# ranback_bottom.net
KiCad netlist of a schematic drawn in EAGLE
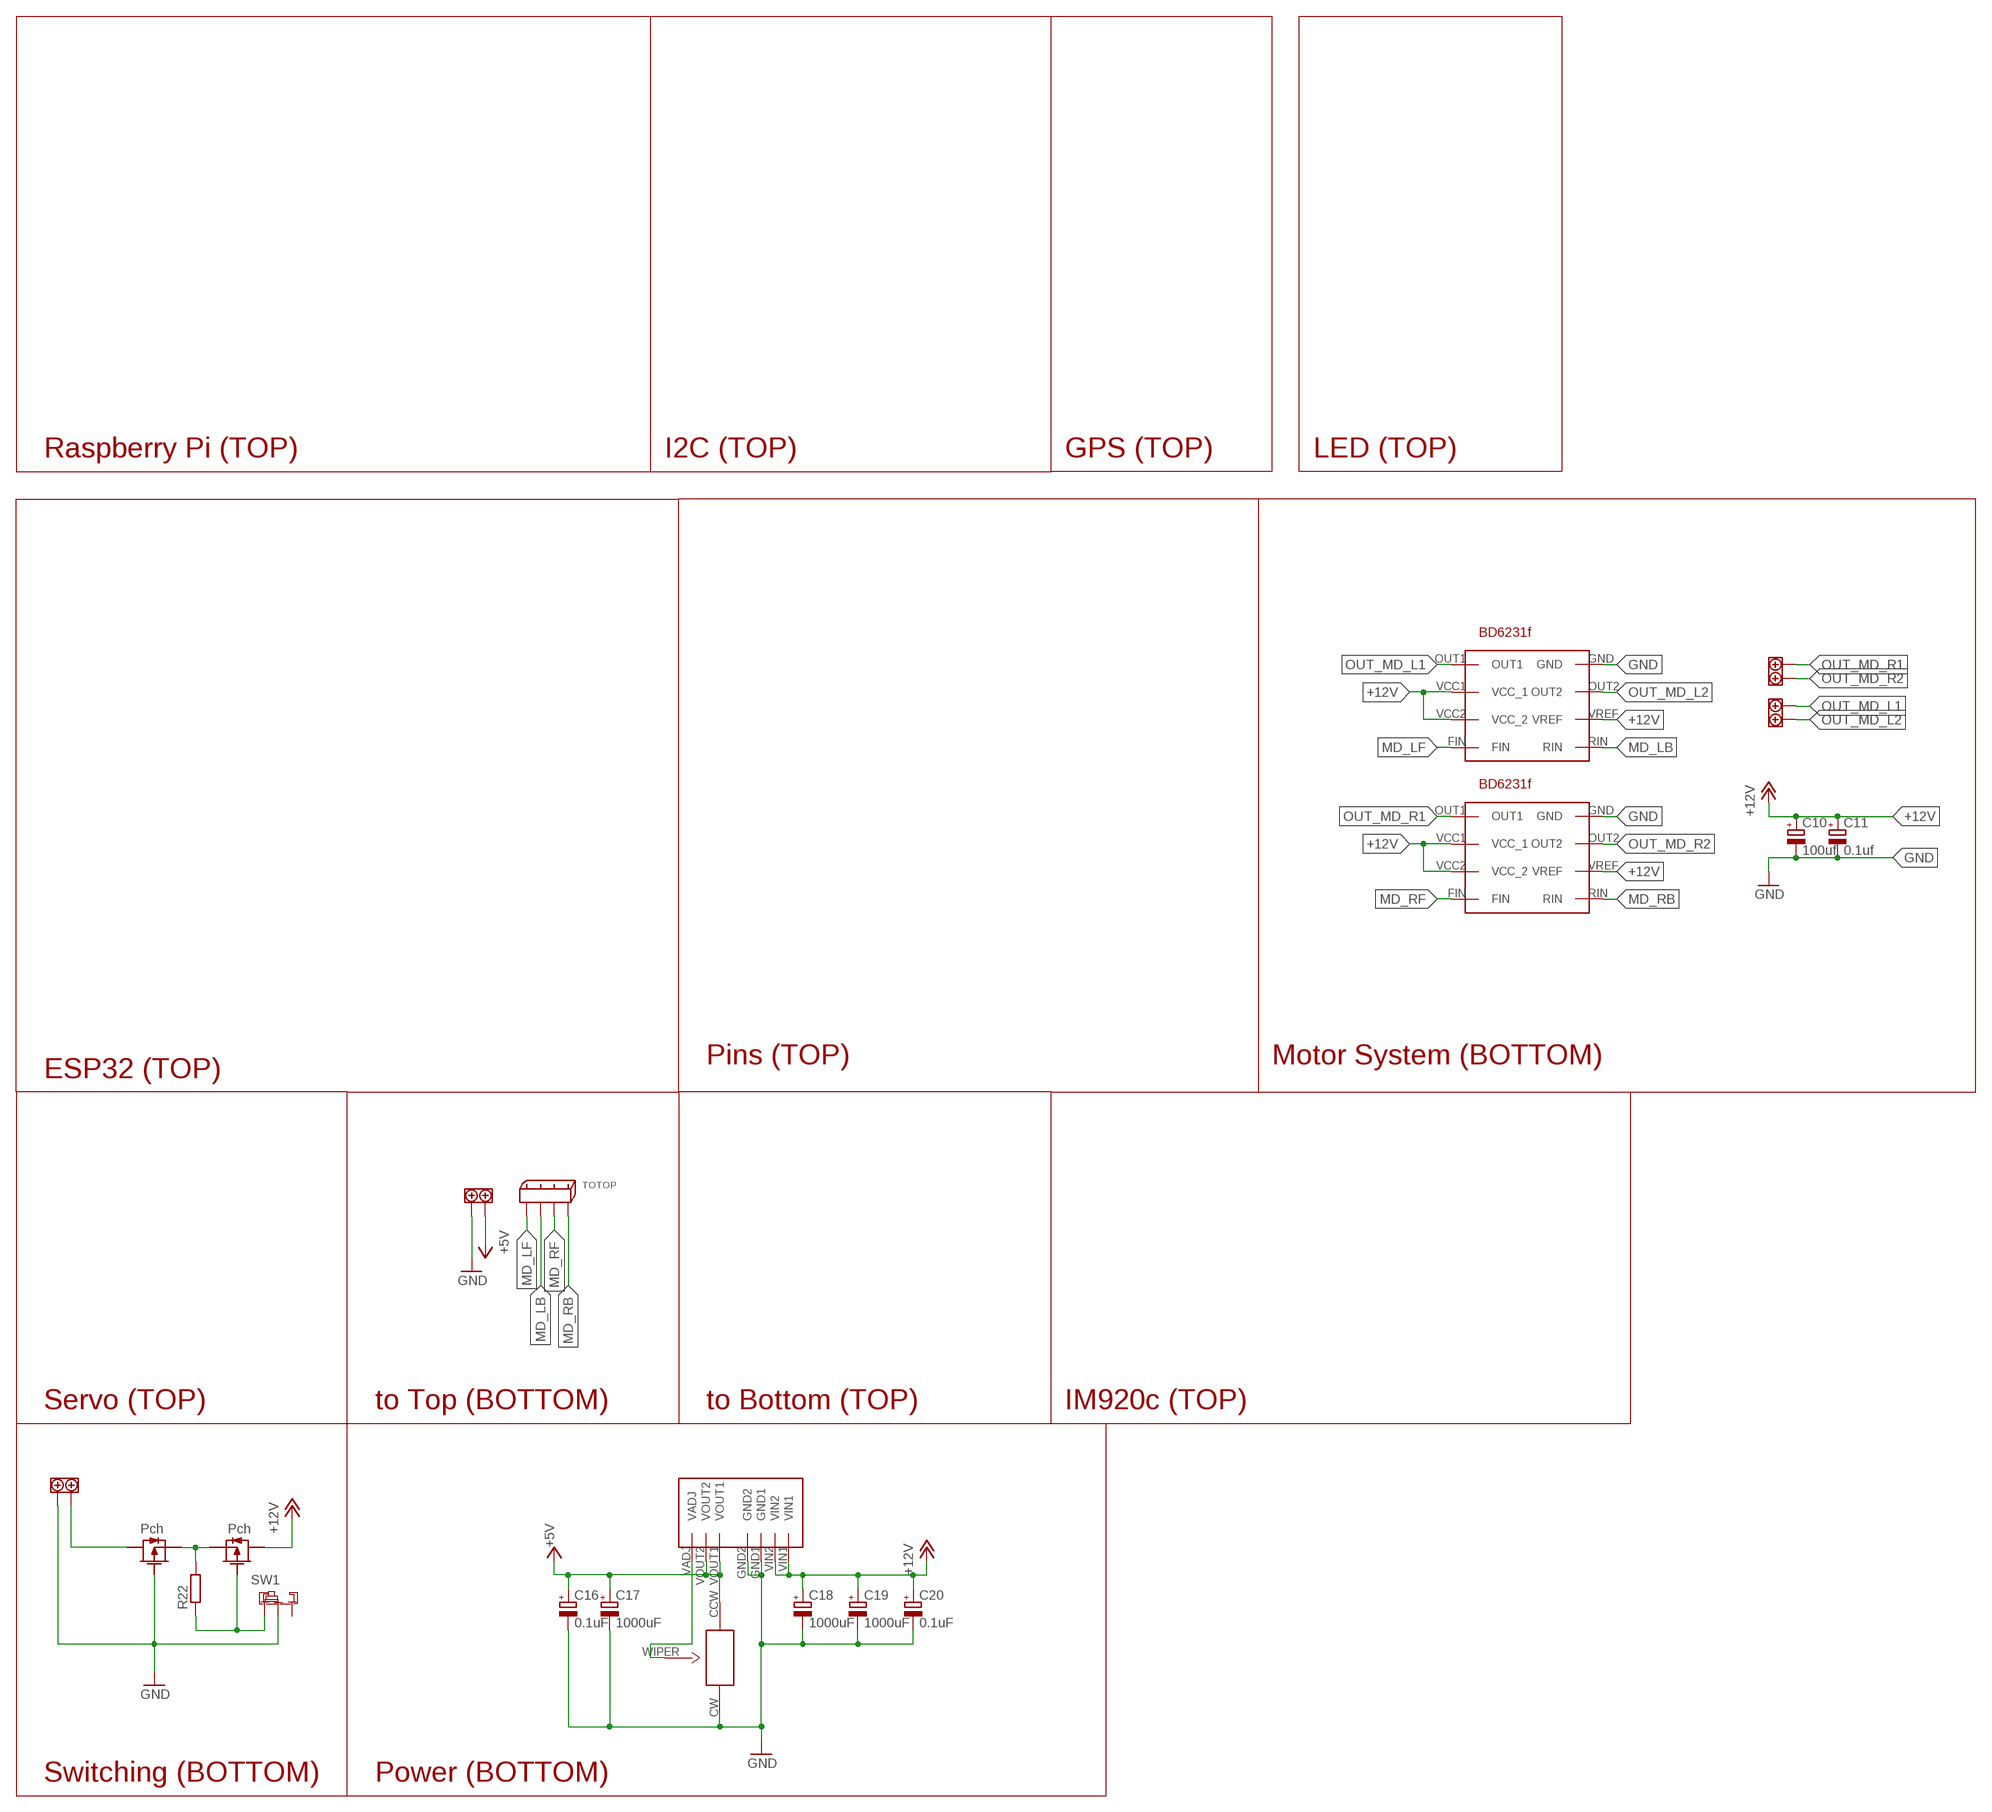
[diagram p0: schematic, sheet 1]

(export (version "E")
  (design (tool "Eeschema 10.0.6"))
  (components
    (comp (ref "100KR1")
      (value "100kR")
      (footprint "eagle-import:3362P")
      (libsource (lib "eagle-import") (part "3362P"))
    )
    (comp (ref "C10")
      (value "100uf")
      (footprint "eagle-import:E2,5-7")
      (libsource (lib "eagle-import") (part "CPOL-EUE2.5-7"))
    )
    (comp (ref "C11")
      (value "0.1uf")
      (footprint "eagle-import:E2,5-7")
      (libsource (lib "eagle-import") (part "CPOL-EUE2.5-7"))
    )
    (comp (ref "C16")
      (value "0.1uF")
      (footprint "eagle-import:E2,5-7")
      (libsource (lib "eagle-import") (part "CPOL-EUE2.5-7"))
    )
    (comp (ref "C17")
      (value "1000uF")
      (footprint "eagle-import:E5-10,5")
      (libsource (lib "eagle-import") (part "CPOL-EUE5-10.5"))
    )
    (comp (ref "C18")
      (value "1000uF")
      (footprint "eagle-import:E5-10,5")
      (libsource (lib "eagle-import") (part "CPOL-EUE5-10.5"))
    )
    (comp (ref "C19")
      (value "1000uF")
      (footprint "eagle-import:E5-10,5")
      (libsource (lib "eagle-import") (part "CPOL-EUE5-10.5"))
    )
    (comp (ref "C20")
      (value "0.1uF")
      (footprint "eagle-import:E2,5-7")
      (libsource (lib "eagle-import") (part "CPOL-EUE2.5-7"))
    )
    (comp (ref "MD_L")
      (value "BD6231F")
      (footprint "eagle-import:BD6231F")
      (libsource (lib "eagle-import") (part "BD6231F"))
    )
    (comp (ref "MD_R")
      (value "BD6231F")
      (footprint "eagle-import:BD6231F")
      (libsource (lib "eagle-import") (part "BD6231F"))
    )
    (comp (ref "R22")
      (value "R-EU_0207/10")
      (footprint "eagle-import:0207_10")
      (libsource (lib "eagle-import") (part "R-EU_0207/10"))
    )
    (comp (ref "SW1")
      (value "SRIDE_SWITCH")
      (footprint "eagle-import:SRIDE_SWITCH")
      (libsource (lib "eagle-import") (part "SRIDE_SWITCH"))
    )
    (comp (ref "TM1")
      (value "TERMINAL_SLOPED_2PIN")
      (footprint "eagle-import:TERMINAL_SLOPED_2PIN")
      (libsource (lib "eagle-import") (part "TERMINAL_SLOPED_2PIN"))
    )
    (comp (ref "TM2")
      (value "TERMINAL_SLOPED_2PIN")
      (footprint "eagle-import:TERMINAL_SLOPED_2PIN")
      (libsource (lib "eagle-import") (part "TERMINAL_SLOPED_2PIN"))
    )
    (comp (ref "TM3")
      (value "TERMINAL_SLOPED_2PIN")
      (footprint "eagle-import:TERMINAL_SLOPED_2PIN")
      (libsource (lib "eagle-import") (part "TERMINAL_SLOPED_2PIN"))
    )
    (comp (ref "TM4")
      (value "TERMINAL_SLOPED_2PIN")
      (footprint "eagle-import:TERMINAL_SLOPED_2PIN")
      (libsource (lib "eagle-import") (part "TERMINAL_SLOPED_2PIN"))
    )
    (comp (ref "TOTOP")
      (value "2.5_MINI-SPOX_4PIN")
      (footprint "eagle-import:2.5_MINI-SPOX_4PIN")
      (libsource (lib "eagle-import") (part "2.5_MINI-SPOX_4PIN"))
    )
    (comp (ref "U$7")
      (value "2SJ681-PCH")
      (footprint "eagle-import:2SJ681")
      (libsource (lib "eagle-import") (part "2SJ681-PCH"))
    )
    (comp (ref "U$8")
      (value "5V3A_KIC-053")
      (footprint "eagle-import:5V3A_KIC-053")
      (libsource (lib "eagle-import") (part "5V3A_KIC-053"))
    )
    (comp (ref "U$10")
      (value "2SJ681-PCH")
      (footprint "eagle-import:2SJ681")
      (libsource (lib "eagle-import") (part "2SJ681-PCH"))
    )
  )
  (nets
    (net (code "1") (name "+5V") (class "Default")
      (node (ref "100KR1") (pin "CCW") (pinfunction "CCW_CCW") (pintype "bidirectional"))
      (node (ref "C16") (pin "+") (pinfunction "+_+") (pintype "passive"))
      (node (ref "C17") (pin "+") (pinfunction "+_+") (pintype "passive"))
      (node (ref "TM4") (pin "1") (pinfunction "1_1") (pintype "bidirectional"))
      (node (ref "U$8") (pin "VOUT1") (pinfunction "VOUT1_VOUT1") (pintype "bidirectional"))
      (node (ref "U$8") (pin "VOUT2") (pinfunction "VOUT2_VOUT2") (pintype "bidirectional"))
    )
    (net (code "2") (name "+12V") (class "Default")
      (node (ref "C10") (pin "+") (pinfunction "+_+") (pintype "passive"))
      (node (ref "C11") (pin "+") (pinfunction "+_+") (pintype "passive"))
      (node (ref "C18") (pin "+") (pinfunction "+_+") (pintype "passive"))
      (node (ref "C19") (pin "+") (pinfunction "+_+") (pintype "passive"))
      (node (ref "C20") (pin "+") (pinfunction "+_+") (pintype "passive"))
      (node (ref "MD_L") (pin "VCC1") (pinfunction "VCC_1_VCC1") (pintype "bidirectional"))
      (node (ref "MD_L") (pin "VCC2") (pinfunction "VCC_2_VCC2") (pintype "bidirectional"))
      (node (ref "MD_L") (pin "VREF") (pinfunction "VREF_VREF") (pintype "bidirectional"))
      (node (ref "MD_R") (pin "VCC1") (pinfunction "VCC_1_VCC1") (pintype "bidirectional"))
      (node (ref "MD_R") (pin "VCC2") (pinfunction "VCC_2_VCC2") (pintype "bidirectional"))
      (node (ref "MD_R") (pin "VREF") (pinfunction "VREF_VREF") (pintype "bidirectional"))
      (node (ref "U$10") (pin "DRAIN") (pinfunction "DRAIN_DRAIN") (pintype "bidirectional"))
      (node (ref "U$8") (pin "VIN1") (pinfunction "VIN1_VIN1") (pintype "bidirectional"))
      (node (ref "U$8") (pin "VIN2") (pinfunction "VIN2_VIN2") (pintype "bidirectional"))
    )
    (net (code "3") (name "GND") (class "Default")
      (node (ref "100KR1") (pin "CW") (pinfunction "CW_CW") (pintype "bidirectional"))
      (node (ref "C10") (pin "-") (pinfunction "-_-") (pintype "passive"))
      (node (ref "C11") (pin "-") (pinfunction "-_-") (pintype "passive"))
      (node (ref "C16") (pin "-") (pinfunction "-_-") (pintype "passive"))
      (node (ref "C17") (pin "-") (pinfunction "-_-") (pintype "passive"))
      (node (ref "C18") (pin "-") (pinfunction "-_-") (pintype "passive"))
      (node (ref "C19") (pin "-") (pinfunction "-_-") (pintype "passive"))
      (node (ref "C20") (pin "-") (pinfunction "-_-") (pintype "passive"))
      (node (ref "MD_L") (pin "GND") (pinfunction "GND_GND") (pintype "bidirectional"))
      (node (ref "MD_R") (pin "GND") (pinfunction "GND_GND") (pintype "bidirectional"))
      (node (ref "SW1") (pin "LR") (pinfunction "LR_LR") (pintype "bidirectional"))
      (node (ref "TM3") (pin "2") (pinfunction "2_2") (pintype "bidirectional"))
      (node (ref "TM4") (pin "2") (pinfunction "2_2") (pintype "bidirectional"))
      (node (ref "U$7") (pin "GATE") (pinfunction "GATE_GATE") (pintype "bidirectional"))
      (node (ref "U$8") (pin "GND1") (pinfunction "GND1_GND1") (pintype "bidirectional"))
      (node (ref "U$8") (pin "GND2") (pinfunction "GND2_GND2") (pintype "bidirectional"))
    )
    (net (code "4") (name "MD_LB") (class "Default")
      (node (ref "MD_L") (pin "RIN") (pinfunction "RIN_RIN") (pintype "bidirectional"))
      (node (ref "TOTOP") (pin "P$2") (pinfunction "2_P$2") (pintype "bidirectional"))
    )
    (net (code "5") (name "MD_LF") (class "Default")
      (node (ref "MD_L") (pin "FIN") (pinfunction "FIN_FIN") (pintype "bidirectional"))
      (node (ref "TOTOP") (pin "P$1") (pinfunction "1_P$1") (pintype "bidirectional"))
    )
    (net (code "6") (name "MD_RB") (class "Default")
      (node (ref "MD_R") (pin "RIN") (pinfunction "RIN_RIN") (pintype "bidirectional"))
      (node (ref "TOTOP") (pin "P$4") (pinfunction "4_P$4") (pintype "bidirectional"))
    )
    (net (code "7") (name "MD_RF") (class "Default")
      (node (ref "MD_R") (pin "FIN") (pinfunction "FIN_FIN") (pintype "bidirectional"))
      (node (ref "TOTOP") (pin "P$3") (pinfunction "3_P$3") (pintype "bidirectional"))
    )
    (net (code "8") (name "Net-(100KR1-PadWIPER)") (class "Default")
      (node (ref "100KR1") (pin "WIPER") (pinfunction "WIPER_WIPER") (pintype "bidirectional"))
      (node (ref "U$8") (pin "VADJ") (pinfunction "VADJ_VADJ") (pintype "bidirectional"))
    )
    (net (code "9") (name "Net-(R22-Pad1)") (class "Default")
      (node (ref "R22") (pin "1") (pinfunction "1_1") (pintype "passive"))
      (node (ref "SW1") (pin "L") (pinfunction "L_L") (pintype "bidirectional"))
      (node (ref "U$10") (pin "GATE") (pinfunction "GATE_GATE") (pintype "bidirectional"))
    )
    (net (code "10") (name "Net-(R22-Pad2)") (class "Default")
      (node (ref "R22") (pin "2") (pinfunction "2_2") (pintype "passive"))
      (node (ref "U$10") (pin "SOURCE") (pinfunction "SOURCE_SOURCE") (pintype "bidirectional"))
      (node (ref "U$7") (pin "SOURCE") (pinfunction "SOURCE_SOURCE") (pintype "bidirectional"))
    )
    (net (code "11") (name "Net-(TM3-Pad1)") (class "Default")
      (node (ref "TM3") (pin "1") (pinfunction "1_1") (pintype "bidirectional"))
      (node (ref "U$7") (pin "DRAIN") (pinfunction "DRAIN_DRAIN") (pintype "bidirectional"))
    )
    (net (code "12") (name "OUT_MD_L1") (class "Default")
      (node (ref "MD_L") (pin "OUT1") (pinfunction "OUT1_OUT1") (pintype "bidirectional"))
      (node (ref "TM2") (pin "1") (pinfunction "1_1") (pintype "bidirectional"))
    )
    (net (code "13") (name "OUT_MD_L2") (class "Default")
      (node (ref "MD_L") (pin "OUT2") (pinfunction "OUT2_OUT2") (pintype "bidirectional"))
      (node (ref "TM2") (pin "2") (pinfunction "2_2") (pintype "bidirectional"))
    )
    (net (code "14") (name "OUT_MD_R1") (class "Default")
      (node (ref "MD_R") (pin "OUT1") (pinfunction "OUT1_OUT1") (pintype "bidirectional"))
      (node (ref "TM1") (pin "1") (pinfunction "1_1") (pintype "bidirectional"))
    )
    (net (code "15") (name "OUT_MD_R2") (class "Default")
      (node (ref "MD_R") (pin "OUT2") (pinfunction "OUT2_OUT2") (pintype "bidirectional"))
      (node (ref "TM1") (pin "2") (pinfunction "2_2") (pintype "bidirectional"))
    )
    (net (code "16") (name "unconnected-(SW1-PadR)") (class "Default")
      (node (ref "SW1") (pin "R") (pinfunction "R_R") (pintype "bidirectional"))
    )
  )
)
